# dc_q84_v2_v1.net
KiCad netlist of a schematic drawn in EAGLE
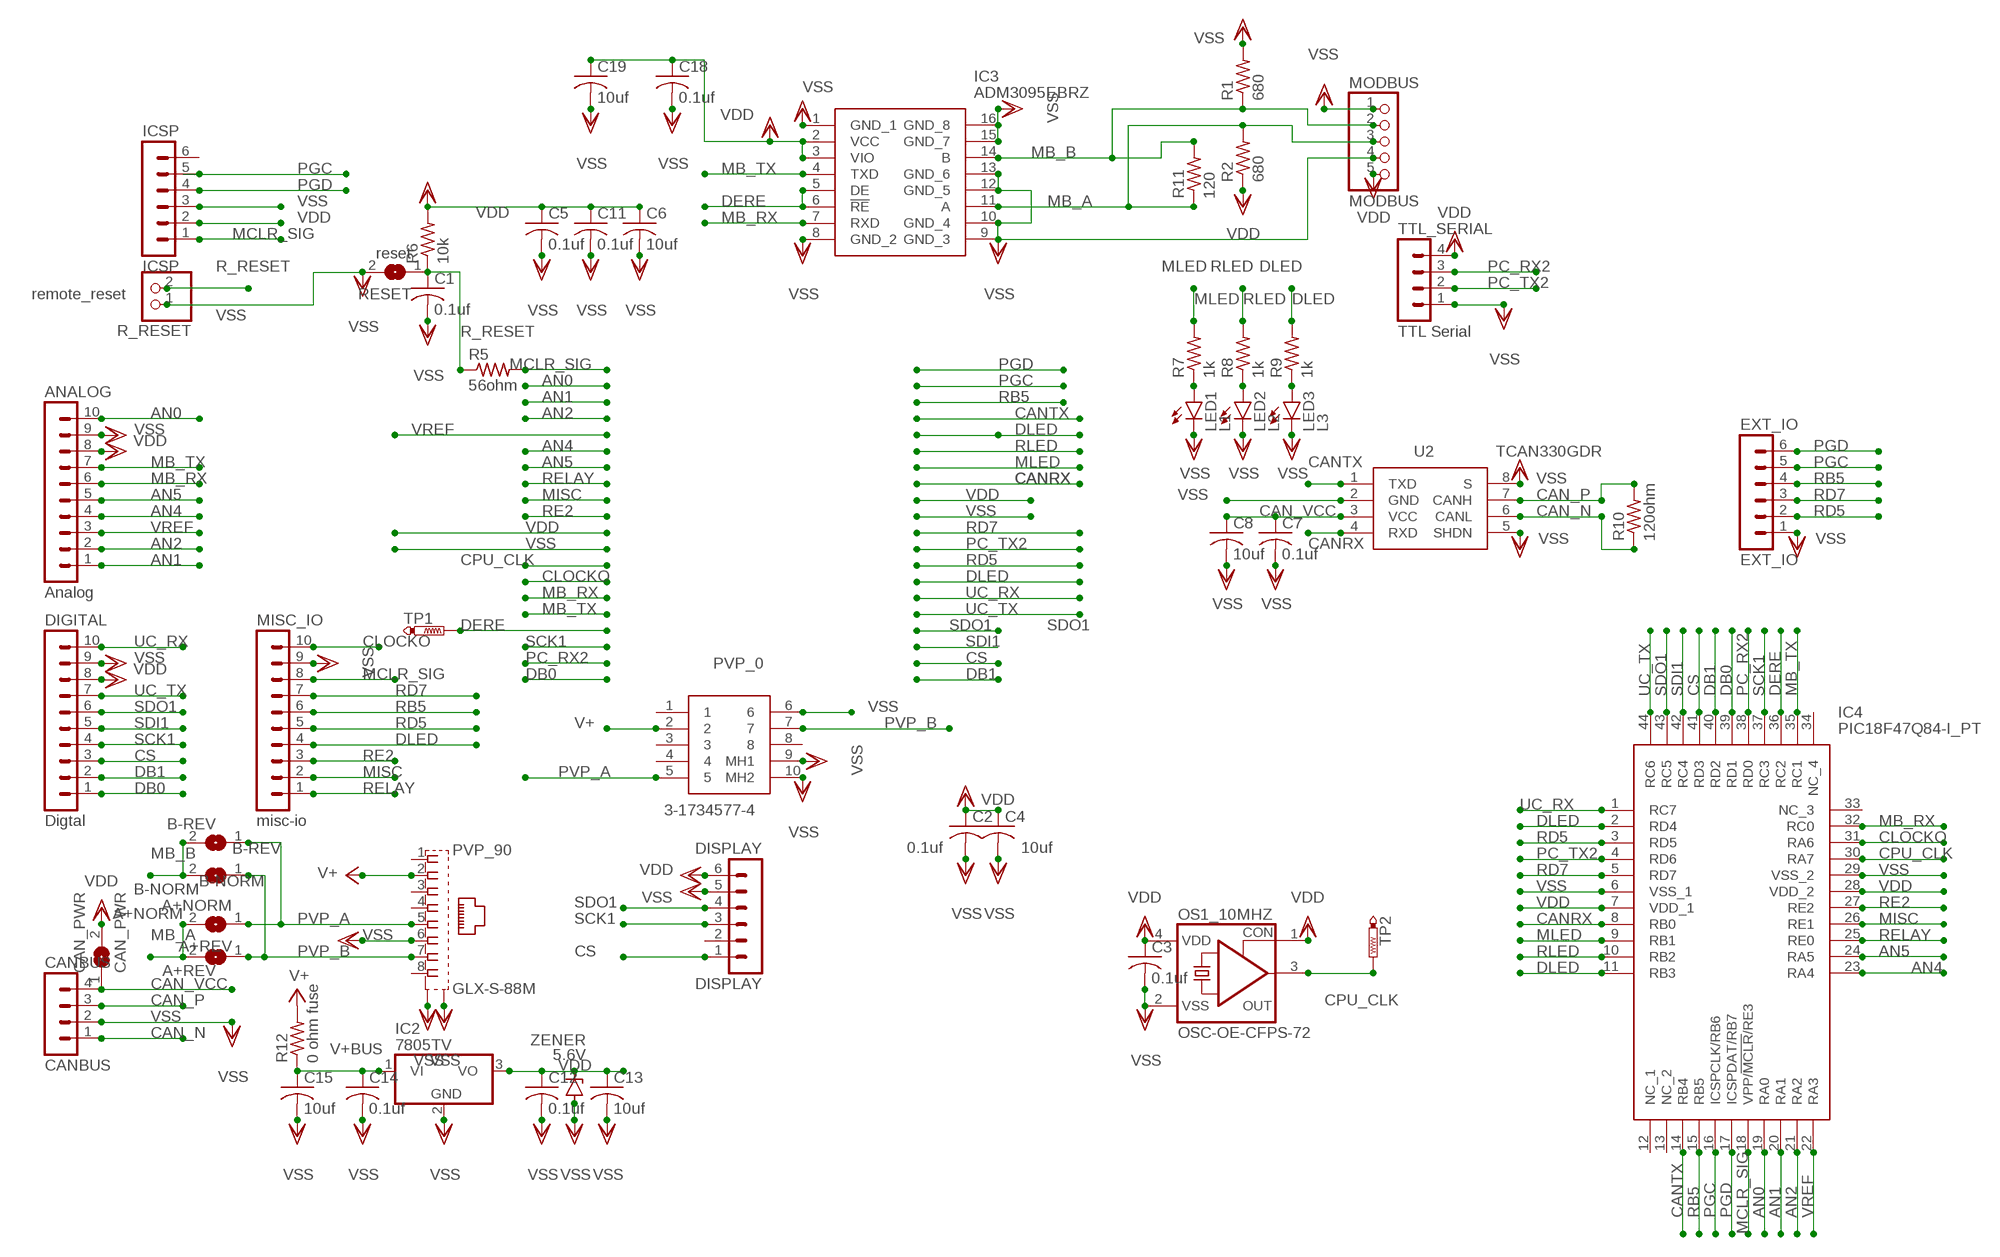
[diagram p0: schematic, sheet 1]

(export (version "E")
  (design (tool "Eeschema 10.0.6"))
  (components
    (comp (ref "A+NORM")
      (value "A+NORM")
      (footprint "eagle-import:SJ")
      (libsource (lib "eagle-import") (part "SJ"))
    )
    (comp (ref "A+REV")
      (value "A+REV")
      (footprint "eagle-import:SJ")
      (libsource (lib "eagle-import") (part "SJ"))
    )
    (comp (ref "ANALOG")
      (value "Analog")
      (footprint "eagle-import:MA10-1")
      (libsource (lib "eagle-import") (part "MA10-1"))
    )
    (comp (ref "B-NORM")
      (value "B-NORM")
      (footprint "eagle-import:SJ")
      (libsource (lib "eagle-import") (part "SJ"))
    )
    (comp (ref "B-REV")
      (value "B-REV")
      (footprint "eagle-import:SJ")
      (libsource (lib "eagle-import") (part "SJ"))
    )
    (comp (ref "C1")
      (value "0.1uf")
      (footprint "eagle-import:C0805")
      (libsource (lib "eagle-import") (part "C-USC0805"))
    )
    (comp (ref "C2")
      (value "0.1uf")
      (footprint "eagle-import:C0805")
      (libsource (lib "eagle-import") (part "C-USC0805"))
    )
    (comp (ref "C3")
      (value "0.1uf")
      (footprint "eagle-import:C0805")
      (libsource (lib "eagle-import") (part "C-USC0805"))
    )
    (comp (ref "C4")
      (value "10uf")
      (footprint "eagle-import:C0805")
      (libsource (lib "eagle-import") (part "C-USC0805"))
    )
    (comp (ref "C5")
      (value "0.1uf")
      (footprint "eagle-import:C0805")
      (libsource (lib "eagle-import") (part "C-USC0805"))
    )
    (comp (ref "C6")
      (value "10uf")
      (footprint "eagle-import:C0805")
      (libsource (lib "eagle-import") (part "C-USC0805"))
    )
    (comp (ref "C7")
      (value "0.1uf")
      (footprint "eagle-import:C0805")
      (libsource (lib "eagle-import") (part "C-USC0805"))
    )
    (comp (ref "C8")
      (value "10uf")
      (footprint "eagle-import:C0805")
      (libsource (lib "eagle-import") (part "C-USC0805"))
    )
    (comp (ref "C11")
      (value "0.1uf")
      (footprint "eagle-import:C0805")
      (libsource (lib "eagle-import") (part "C-USC0805"))
    )
    (comp (ref "C12")
      (value "0.1uf")
      (footprint "eagle-import:C0805")
      (libsource (lib "eagle-import") (part "C-USC0805"))
    )
    (comp (ref "C13")
      (value "10uf")
      (footprint "eagle-import:C0805")
      (libsource (lib "eagle-import") (part "C-USC0805"))
    )
    (comp (ref "C14")
      (value "0.1uf")
      (footprint "eagle-import:C0805")
      (libsource (lib "eagle-import") (part "C-USC0805"))
    )
    (comp (ref "C15")
      (value "10uf")
      (footprint "eagle-import:C0805")
      (libsource (lib "eagle-import") (part "C-USC0805"))
    )
    (comp (ref "C18")
      (value "0.1uf")
      (footprint "eagle-import:C0805")
      (libsource (lib "eagle-import") (part "C-USC0805"))
    )
    (comp (ref "C19")
      (value "10uf")
      (footprint "eagle-import:C0805")
      (libsource (lib "eagle-import") (part "C-USC0805"))
    )
    (comp (ref "CANBUS")
      (value "CANBUS")
      (footprint "eagle-import:MA04-1")
      (libsource (lib "eagle-import") (part "MA04-1"))
    )
    (comp (ref "CAN_PWR")
      (value "CAN_PWR")
      (footprint "eagle-import:SJ")
      (libsource (lib "eagle-import") (part "SJ"))
    )
    (comp (ref "DIGITAL")
      (value "Digtal")
      (footprint "eagle-import:MA10-1")
      (libsource (lib "eagle-import") (part "MA10-1"))
    )
    (comp (ref "DISPLAY")
      (value "DISPLAY")
      (footprint "eagle-import:MA06-1")
      (libsource (lib "eagle-import") (part "MA06-1"))
    )
    (comp (ref "EXT_IO")
      (value "EXT_IO")
      (footprint "eagle-import:MA06-1")
      (libsource (lib "eagle-import") (part "MA06-1"))
    )
    (comp (ref "IC2")
      (value "7805TV")
      (footprint "eagle-import:TO220V")
      (libsource (lib "eagle-import") (part "78TV05"))
    )
    (comp (ref "IC3")
      (value "ADM3095EBRZ")
      (footprint "eagle-import:SOIC127P600X175-16N")
      (fields (field (name "MOUSER_PART_NUMBER") "584-ADM3095EBRZ"))
      (libsource (lib "eagle-import") (part "ADM3095EBRZ"))
    )
    (comp (ref "IC4")
      (value "PIC18F47Q84-I_PT")
      (footprint "eagle-import:QFP80P1200X1200X120-44N")
      (fields
        (field (name "MANUFACTURER_PART_NUMBER") "PIC18F47Q84-I/PT")
        (field (name "MOUSER_PART_NUMBER") "579-PIC18F47Q84-I/PT")
      )
      (libsource (lib "eagle-import") (part "PIC18F47Q84-I_PT"))
    )
    (comp (ref "ICSP")
      (value "ICSP")
      (footprint "eagle-import:MA06-1")
      (libsource (lib "eagle-import") (part "MA06-1"))
    )
    (comp (ref "LED1")
      (value "L1")
      (footprint "eagle-import:CHIPLED_0805")
      (libsource (lib "eagle-import") (part "LEDCHIPLED_0805"))
    )
    (comp (ref "LED2")
      (value "L2")
      (footprint "eagle-import:CHIPLED_0805")
      (libsource (lib "eagle-import") (part "LEDCHIPLED_0805"))
    )
    (comp (ref "LED3")
      (value "L3")
      (footprint "eagle-import:CHIPLED_0805")
      (libsource (lib "eagle-import") (part "LEDCHIPLED_0805"))
    )
    (comp (ref "MISC_IO")
      (value "misc-io")
      (footprint "eagle-import:MA10-1")
      (libsource (lib "eagle-import") (part "MA10-1"))
    )
    (comp (ref "MODBUS")
      (value "MODBUS")
      (footprint "eagle-import:1X05")
      (libsource (lib "eagle-import") (part "PINHD-1X5"))
    )
    (comp (ref "OS1_10MHZ")
      (value "OSC-OE-CFPS-72")
      (footprint "eagle-import:7.2X5.2-4-PAD")
      (libsource (lib "eagle-import") (part "OSC-OE-CFPS-72"))
    )
    (comp (ref "PVP_0")
      (value "3-1734577-4")
      (footprint "eagle-import:317345774")
      (fields (field (name "MOUSER_PART_NUMBER") "571-3-1734577-4"))
      (libsource (lib "eagle-import") (part "3-1734577-4"))
    )
    (comp (ref "PVP_90")
      (value "GLX-S-88M")
      (footprint "eagle-import:GLX-S-88M")
      (libsource (lib "eagle-import") (part "GLX-S-88M"))
    )
    (comp (ref "R1")
      (value "680")
      (footprint "eagle-import:R0805")
      (libsource (lib "eagle-import") (part "R-US_R0805"))
    )
    (comp (ref "R2")
      (value "680")
      (footprint "eagle-import:R0805")
      (libsource (lib "eagle-import") (part "R-US_R0805"))
    )
    (comp (ref "R5")
      (value "56ohm")
      (footprint "eagle-import:R0805")
      (libsource (lib "eagle-import") (part "R-US_R0805"))
    )
    (comp (ref "R6")
      (value "10k")
      (footprint "eagle-import:R0805")
      (libsource (lib "eagle-import") (part "R-US_R0805"))
    )
    (comp (ref "R7")
      (value "1k")
      (footprint "eagle-import:R0805")
      (libsource (lib "eagle-import") (part "R-US_R0805"))
    )
    (comp (ref "R8")
      (value "1k")
      (footprint "eagle-import:R0805")
      (libsource (lib "eagle-import") (part "R-US_R0805"))
    )
    (comp (ref "R9")
      (value "1k")
      (footprint "eagle-import:R0805")
      (libsource (lib "eagle-import") (part "R-US_R0805"))
    )
    (comp (ref "R10")
      (value "120ohm")
      (footprint "eagle-import:R0805")
      (libsource (lib "eagle-import") (part "R-US_R0805"))
    )
    (comp (ref "R11")
      (value "120")
      (footprint "eagle-import:R0805")
      (libsource (lib "eagle-import") (part "R-US_R0805"))
    )
    (comp (ref "R12")
      (value "0 ohm fuse")
      (footprint "eagle-import:R1206")
      (libsource (lib "eagle-import") (part "R-US_R1206"))
    )
    (comp (ref "RESET")
      (value "reset")
      (footprint "eagle-import:SJ")
      (libsource (lib "eagle-import") (part "SJ"))
    )
    (comp (ref "R_RESET")
      (value "remote_reset")
      (footprint "eagle-import:1X02")
      (libsource (lib "eagle-import") (part "PINHD-1X2"))
    )
    (comp (ref "TP1")
      (value "PTR1PAD1-13")
      (footprint "eagle-import:P1-13")
      (libsource (lib "eagle-import") (part "PTR1PAD1-13"))
    )
    (comp (ref "TP2")
      (value "PTR1PAD1-13")
      (footprint "eagle-import:P1-13")
      (libsource (lib "eagle-import") (part "PTR1PAD1-13"))
    )
    (comp (ref "TTL_SERIAL")
      (value "TTL Serial")
      (footprint "eagle-import:MA04-1")
      (libsource (lib "eagle-import") (part "MA04-1"))
    )
    (comp (ref "U2")
      (value "TCAN330GDR")
      (footprint "eagle-import:SOIC127P600X175-8N")
      (fields (field (name "MOUSER_PART_NUMBER") "595-TCAN330GDR"))
      (libsource (lib "eagle-import") (part "TCAN330GDR"))
    )
    (comp (ref "ZENER")
      (value "5.6V")
      (footprint "eagle-import:SMB")
      (libsource (lib "eagle-import") (part "ZENER-DIODESMB"))
    )
  )
  (nets
    (net (code "1") (name "/AN0") (class "Default")
      (node (ref "ANALOG") (pin "10") (pinfunction "10_10") (pintype "passive"))
      (node (ref "IC4") (pin "19") (pinfunction "RA0_19") (pintype "bidirectional"))
    )
    (net (code "2") (name "/AN1") (class "Default")
      (node (ref "ANALOG") (pin "1") (pinfunction "1_1") (pintype "passive"))
      (node (ref "IC4") (pin "20") (pinfunction "RA1_20") (pintype "bidirectional"))
    )
    (net (code "3") (name "/AN2") (class "Default")
      (node (ref "ANALOG") (pin "2") (pinfunction "2_2") (pintype "passive"))
      (node (ref "IC4") (pin "21") (pinfunction "RA2_21") (pintype "bidirectional"))
    )
    (net (code "4") (name "/AN4") (class "Default")
      (node (ref "ANALOG") (pin "4") (pinfunction "4_4") (pintype "passive"))
      (node (ref "IC4") (pin "23") (pinfunction "RA4_23") (pintype "bidirectional"))
    )
    (net (code "5") (name "/AN5") (class "Default")
      (node (ref "ANALOG") (pin "5") (pinfunction "5_5") (pintype "passive"))
      (node (ref "IC4") (pin "24") (pinfunction "RA5_24") (pintype "bidirectional"))
    )
    (net (code "6") (name "/CANRX") (class "Default")
      (node (ref "IC4") (pin "8") (pinfunction "RB0_8") (pintype "bidirectional"))
      (node (ref "U2") (pin "4") (pinfunction "RXD_4") (pintype "output"))
    )
    (net (code "7") (name "/CANTX") (class "Default")
      (node (ref "IC4") (pin "14") (pinfunction "RB4_14") (pintype "bidirectional"))
      (node (ref "U2") (pin "1") (pinfunction "TXD_1") (pintype "input"))
    )
    (net (code "8") (name "/CAN_N") (class "Default")
      (node (ref "CANBUS") (pin "1") (pinfunction "1_1") (pintype "passive"))
      (node (ref "R10") (pin "1") (pinfunction "1_1") (pintype "passive"))
      (node (ref "U2") (pin "6") (pinfunction "CANL_6") (pintype "bidirectional"))
    )
    (net (code "9") (name "/CAN_P") (class "Default")
      (node (ref "CANBUS") (pin "3") (pinfunction "3_3") (pintype "passive"))
      (node (ref "R10") (pin "2") (pinfunction "2_2") (pintype "passive"))
      (node (ref "U2") (pin "7") (pinfunction "CANH_7") (pintype "bidirectional"))
    )
    (net (code "10") (name "/CAN_VCC") (class "Default")
      (node (ref "C7") (pin "1") (pinfunction "1_1") (pintype "passive"))
      (node (ref "C8") (pin "1") (pinfunction "1_1") (pintype "passive"))
      (node (ref "CANBUS") (pin "4") (pinfunction "4_4") (pintype "passive"))
      (node (ref "CAN_PWR") (pin "1") (pinfunction "1_1") (pintype "passive"))
      (node (ref "U2") (pin "3") (pinfunction "VCC_3") (pintype "power_in"))
    )
    (net (code "11") (name "/CLOCKO") (class "Default")
      (node (ref "IC4") (pin "31") (pinfunction "RA6_31") (pintype "bidirectional"))
      (node (ref "MISC_IO") (pin "10") (pinfunction "10_10") (pintype "passive"))
    )
    (net (code "12") (name "/CPU_CLK") (class "Default")
      (node (ref "IC4") (pin "30") (pinfunction "RA7_30") (pintype "bidirectional"))
      (node (ref "OS1_10MHZ") (pin "3") (pinfunction "OUT_3") (pintype "output"))
      (node (ref "TP2") (pin "TP") (pinfunction "TP_TP") (pintype "input"))
    )
    (net (code "13") (name "/CS") (class "Default")
      (node (ref "DIGITAL") (pin "3") (pinfunction "3_3") (pintype "passive"))
      (node (ref "DISPLAY") (pin "1") (pinfunction "1_1") (pintype "passive"))
      (node (ref "IC4") (pin "41") (pinfunction "RD3_41") (pintype "bidirectional"))
    )
    (net (code "14") (name "/DB0") (class "Default")
      (node (ref "DIGITAL") (pin "1") (pinfunction "1_1") (pintype "passive"))
      (node (ref "IC4") (pin "39") (pinfunction "RD1_39") (pintype "bidirectional"))
    )
    (net (code "15") (name "/DB1") (class "Default")
      (node (ref "DIGITAL") (pin "2") (pinfunction "2_2") (pintype "passive"))
      (node (ref "IC4") (pin "40") (pinfunction "RD2_40") (pintype "bidirectional"))
    )
    (net (code "16") (name "/DERE") (class "Default")
      (node (ref "IC3") (pin "5") (pinfunction "DE_5") (pintype "input"))
      (node (ref "IC3") (pin "6") (pinfunction "~{RE}_6") (pintype "input"))
      (node (ref "IC4") (pin "36") (pinfunction "RC2_36") (pintype "bidirectional"))
      (node (ref "TP1") (pin "TP") (pinfunction "TP_TP") (pintype "input"))
    )
    (net (code "17") (name "/DLED") (class "Default")
      (node (ref "IC4") (pin "11") (pinfunction "RB3_11") (pintype "bidirectional"))
      (node (ref "IC4") (pin "2") (pinfunction "RD4_2") (pintype "bidirectional"))
      (node (ref "MISC_IO") (pin "4") (pinfunction "4_4") (pintype "passive"))
      (node (ref "R9") (pin "2") (pinfunction "2_2") (pintype "passive"))
    )
    (net (code "18") (name "/MB_A") (class "Default")
      (node (ref "A+NORM") (pin "2") (pinfunction "2_2") (pintype "passive"))
      (node (ref "A+REV") (pin "2") (pinfunction "2_2") (pintype "passive"))
      (node (ref "IC3") (pin "11") (pinfunction "A_11") (pintype "bidirectional"))
      (node (ref "MODBUS") (pin "3") (pinfunction "3_3") (pintype "passive"))
      (node (ref "R11") (pin "1") (pinfunction "1_1") (pintype "passive"))
      (node (ref "R2") (pin "2") (pinfunction "2_2") (pintype "passive"))
    )
    (net (code "19") (name "/MB_B") (class "Default")
      (node (ref "B-NORM") (pin "2") (pinfunction "2_2") (pintype "passive"))
      (node (ref "B-REV") (pin "2") (pinfunction "2_2") (pintype "passive"))
      (node (ref "IC3") (pin "14") (pinfunction "B_14") (pintype "bidirectional"))
      (node (ref "MODBUS") (pin "2") (pinfunction "2_2") (pintype "passive"))
      (node (ref "R1") (pin "1") (pinfunction "1_1") (pintype "passive"))
      (node (ref "R11") (pin "2") (pinfunction "2_2") (pintype "passive"))
    )
    (net (code "20") (name "/MB_RX") (class "Default")
      (node (ref "ANALOG") (pin "6") (pinfunction "6_6") (pintype "passive"))
      (node (ref "IC3") (pin "7") (pinfunction "RXD_7") (pintype "output"))
      (node (ref "IC4") (pin "32") (pinfunction "RC0_32") (pintype "bidirectional"))
    )
    (net (code "21") (name "/MB_TX") (class "Default")
      (node (ref "ANALOG") (pin "7") (pinfunction "7_7") (pintype "passive"))
      (node (ref "IC3") (pin "4") (pinfunction "TXD_4") (pintype "input"))
      (node (ref "IC4") (pin "35") (pinfunction "RC1_35") (pintype "bidirectional"))
    )
    (net (code "22") (name "/MCLR_SIG") (class "Default")
      (node (ref "IC4") (pin "18") (pinfunction "VPP/~{MCLR}/RE3_18") (pintype "bidirectional"))
      (node (ref "ICSP") (pin "1") (pinfunction "1_1") (pintype "passive"))
      (node (ref "MISC_IO") (pin "8") (pinfunction "8_8") (pintype "passive"))
      (node (ref "R5") (pin "2") (pinfunction "2_2") (pintype "passive"))
    )
    (net (code "23") (name "/MISC") (class "Default")
      (node (ref "IC4") (pin "26") (pinfunction "RE1_26") (pintype "bidirectional"))
      (node (ref "MISC_IO") (pin "2") (pinfunction "2_2") (pintype "passive"))
    )
    (net (code "24") (name "/MLED") (class "Default")
      (node (ref "IC4") (pin "9") (pinfunction "RB1_9") (pintype "bidirectional"))
      (node (ref "R7") (pin "2") (pinfunction "2_2") (pintype "passive"))
    )
    (net (code "25") (name "/PC_RX2") (class "Default")
      (node (ref "IC4") (pin "38") (pinfunction "RD0_38") (pintype "bidirectional"))
      (node (ref "TTL_SERIAL") (pin "3") (pinfunction "3_3") (pintype "passive"))
    )
    (net (code "26") (name "/PC_TX2") (class "Default")
      (node (ref "IC4") (pin "4") (pinfunction "RD6_4") (pintype "bidirectional"))
      (node (ref "TTL_SERIAL") (pin "2") (pinfunction "2_2") (pintype "passive"))
    )
    (net (code "27") (name "/PGC") (class "Default")
      (node (ref "EXT_IO") (pin "5") (pinfunction "5_5") (pintype "passive"))
      (node (ref "IC4") (pin "16") (pinfunction "ICSPCLK/RB6_16") (pintype "bidirectional"))
      (node (ref "ICSP") (pin "5") (pinfunction "5_5") (pintype "passive"))
    )
    (net (code "28") (name "/PGD") (class "Default")
      (node (ref "EXT_IO") (pin "6") (pinfunction "6_6") (pintype "passive"))
      (node (ref "IC4") (pin "17") (pinfunction "ICSPDAT/RB7_17") (pintype "bidirectional"))
      (node (ref "ICSP") (pin "4") (pinfunction "4_4") (pintype "passive"))
    )
    (net (code "29") (name "/PVP_A") (class "Default")
      (node (ref "A+NORM") (pin "1") (pinfunction "1_1") (pintype "passive"))
      (node (ref "B-REV") (pin "1") (pinfunction "1_1") (pintype "passive"))
      (node (ref "PVP_0") (pin "5") (pinfunction "5_5") (pintype "bidirectional"))
      (node (ref "PVP_90") (pin "5") (pinfunction "5_5") (pintype "passive"))
    )
    (net (code "30") (name "/PVP_B") (class "Default")
      (node (ref "A+REV") (pin "1") (pinfunction "1_1") (pintype "passive"))
      (node (ref "B-NORM") (pin "1") (pinfunction "1_1") (pintype "passive"))
      (node (ref "PVP_0") (pin "7") (pinfunction "7_7") (pintype "bidirectional"))
      (node (ref "PVP_90") (pin "7") (pinfunction "7_7") (pintype "passive"))
    )
    (net (code "31") (name "/RB5") (class "Default")
      (node (ref "EXT_IO") (pin "4") (pinfunction "4_4") (pintype "passive"))
      (node (ref "IC4") (pin "15") (pinfunction "RB5_15") (pintype "bidirectional"))
      (node (ref "MISC_IO") (pin "6") (pinfunction "6_6") (pintype "passive"))
    )
    (net (code "32") (name "/RD5") (class "Default")
      (node (ref "EXT_IO") (pin "2") (pinfunction "2_2") (pintype "passive"))
      (node (ref "IC4") (pin "3") (pinfunction "RD5_3") (pintype "bidirectional"))
      (node (ref "MISC_IO") (pin "5") (pinfunction "5_5") (pintype "passive"))
    )
    (net (code "33") (name "/RD7") (class "Default")
      (node (ref "EXT_IO") (pin "3") (pinfunction "3_3") (pintype "passive"))
      (node (ref "IC4") (pin "5") (pinfunction "RD7_5") (pintype "bidirectional"))
      (node (ref "MISC_IO") (pin "7") (pinfunction "7_7") (pintype "passive"))
    )
    (net (code "34") (name "/RE2") (class "Default")
      (node (ref "IC4") (pin "27") (pinfunction "RE2_27") (pintype "bidirectional"))
      (node (ref "MISC_IO") (pin "3") (pinfunction "3_3") (pintype "passive"))
    )
    (net (code "35") (name "/RELAY") (class "Default")
      (node (ref "IC4") (pin "25") (pinfunction "RE0_25") (pintype "bidirectional"))
      (node (ref "MISC_IO") (pin "1") (pinfunction "1_1") (pintype "passive"))
    )
    (net (code "36") (name "/RLED") (class "Default")
      (node (ref "IC4") (pin "10") (pinfunction "RB2_10") (pintype "bidirectional"))
      (node (ref "R8") (pin "2") (pinfunction "2_2") (pintype "passive"))
    )
    (net (code "37") (name "/R_RESET") (class "Default")
      (node (ref "C1") (pin "1") (pinfunction "1_1") (pintype "passive"))
      (node (ref "R5") (pin "1") (pinfunction "1_1") (pintype "passive"))
      (node (ref "R6") (pin "1") (pinfunction "1_1") (pintype "passive"))
      (node (ref "RESET") (pin "1") (pinfunction "1_1") (pintype "passive"))
      (node (ref "R_RESET") (pin "2") (pinfunction "2_2") (pintype "passive"))
    )
    (net (code "38") (name "/SCK1") (class "Default")
      (node (ref "DIGITAL") (pin "4") (pinfunction "4_4") (pintype "passive"))
      (node (ref "DISPLAY") (pin "3") (pinfunction "3_3") (pintype "passive"))
      (node (ref "IC4") (pin "37") (pinfunction "RC3_37") (pintype "bidirectional"))
    )
    (net (code "39") (name "/SDI1") (class "Default")
      (node (ref "DIGITAL") (pin "5") (pinfunction "5_5") (pintype "passive"))
      (node (ref "IC4") (pin "42") (pinfunction "RC4_42") (pintype "bidirectional"))
    )
    (net (code "40") (name "/SDO1") (class "Default")
      (node (ref "DIGITAL") (pin "6") (pinfunction "6_6") (pintype "passive"))
      (node (ref "DISPLAY") (pin "4") (pinfunction "4_4") (pintype "passive"))
      (node (ref "IC4") (pin "43") (pinfunction "RC5_43") (pintype "bidirectional"))
    )
    (net (code "41") (name "/UC_RX") (class "Default")
      (node (ref "DIGITAL") (pin "10") (pinfunction "10_10") (pintype "passive"))
      (node (ref "IC4") (pin "1") (pinfunction "RC7_1") (pintype "bidirectional"))
    )
    (net (code "42") (name "/UC_TX") (class "Default")
      (node (ref "DIGITAL") (pin "7") (pinfunction "7_7") (pintype "passive"))
      (node (ref "IC4") (pin "44") (pinfunction "RC6_44") (pintype "bidirectional"))
    )
    (net (code "43") (name "/V+BUS") (class "Default")
      (node (ref "C14") (pin "1") (pinfunction "1_1") (pintype "passive"))
      (node (ref "C15") (pin "1") (pinfunction "1_1") (pintype "passive"))
      (node (ref "IC2") (pin "1") (pinfunction "VI_1") (pintype "input"))
      (node (ref "R12") (pin "1") (pinfunction "1_1") (pintype "passive"))
    )
    (net (code "44") (name "/VREF") (class "Default")
      (node (ref "ANALOG") (pin "3") (pinfunction "3_3") (pintype "passive"))
      (node (ref "IC4") (pin "22") (pinfunction "RA3_22") (pintype "bidirectional"))
    )
    (net (code "45") (name "Net-(LED1-PadA)") (class "Default")
      (node (ref "LED1") (pin "A") (pinfunction "A_A") (pintype "passive"))
      (node (ref "R7") (pin "1") (pinfunction "1_1") (pintype "passive"))
    )
    (net (code "46") (name "Net-(LED2-PadA)") (class "Default")
      (node (ref "LED2") (pin "A") (pinfunction "A_A") (pintype "passive"))
      (node (ref "R8") (pin "1") (pinfunction "1_1") (pintype "passive"))
    )
    (net (code "47") (name "Net-(LED3-PadA)") (class "Default")
      (node (ref "LED3") (pin "A") (pinfunction "A_A") (pintype "passive"))
      (node (ref "R9") (pin "1") (pinfunction "1_1") (pintype "passive"))
    )
    (net (code "48") (name "V+") (class "Default")
      (node (ref "PVP_0") (pin "2") (pinfunction "2_2") (pintype "bidirectional"))
      (node (ref "PVP_90") (pin "2") (pinfunction "2_2") (pintype "passive"))
      (node (ref "R12") (pin "2") (pinfunction "2_2") (pintype "passive"))
    )
    (net (code "49") (name "VDD") (class "Default")
      (node (ref "ANALOG") (pin "8") (pinfunction "8_8") (pintype "passive"))
      (node (ref "C11") (pin "1") (pinfunction "1_1") (pintype "passive"))
      (node (ref "C12") (pin "1") (pinfunction "1_1") (pintype "passive"))
      (node (ref "C13") (pin "1") (pinfunction "1_1") (pintype "passive"))
      (node (ref "C18") (pin "1") (pinfunction "1_1") (pintype "passive"))
      (node (ref "C19") (pin "1") (pinfunction "1_1") (pintype "passive"))
      (node (ref "C2") (pin "1") (pinfunction "1_1") (pintype "passive"))
      (node (ref "C3") (pin "1") (pinfunction "1_1") (pintype "passive"))
      (node (ref "C4") (pin "1") (pinfunction "1_1") (pintype "passive"))
      (node (ref "C5") (pin "1") (pinfunction "1_1") (pintype "passive"))
      (node (ref "C6") (pin "1") (pinfunction "1_1") (pintype "passive"))
      (node (ref "CAN_PWR") (pin "2") (pinfunction "2_2") (pintype "passive"))
      (node (ref "DIGITAL") (pin "8") (pinfunction "8_8") (pintype "passive"))
      (node (ref "DISPLAY") (pin "6") (pinfunction "6_6") (pintype "passive"))
      (node (ref "IC2") (pin "3") (pinfunction "VO_3") (pintype "passive"))
      (node (ref "IC3") (pin "2") (pinfunction "VCC_2") (pintype "power_in"))
      (node (ref "IC3") (pin "3") (pinfunction "VIO_3") (pintype "power_in"))
      (node (ref "IC4") (pin "28") (pinfunction "VDD_2_28") (pintype "bidirectional"))
      (node (ref "IC4") (pin "7") (pinfunction "VDD_1_7") (pintype "bidirectional"))
      (node (ref "ICSP") (pin "2") (pinfunction "2_2") (pintype "passive"))
      (node (ref "MODBUS") (pin "5") (pinfunction "5_5") (pintype "passive"))
      (node (ref "OS1_10MHZ") (pin "1") (pinfunction "CON_1") (pintype "input"))
      (node (ref "OS1_10MHZ") (pin "4") (pinfunction "VDD_4") (pintype "power_in"))
      (node (ref "R2") (pin "1") (pinfunction "1_1") (pintype "passive"))
      (node (ref "R6") (pin "2") (pinfunction "2_2") (pintype "passive"))
      (node (ref "TTL_SERIAL") (pin "4") (pinfunction "4_4") (pintype "passive"))
      (node (ref "ZENER") (pin "C") (pinfunction "C_C") (pintype "passive"))
    )
    (net (code "50") (name "VSS") (class "Default")
      (node (ref "ANALOG") (pin "9") (pinfunction "9_9") (pintype "passive"))
      (node (ref "C1") (pin "2") (pinfunction "2_2") (pintype "passive"))
      (node (ref "C11") (pin "2") (pinfunction "2_2") (pintype "passive"))
      (node (ref "C12") (pin "2") (pinfunction "2_2") (pintype "passive"))
      (node (ref "C13") (pin "2") (pinfunction "2_2") (pintype "passive"))
      (node (ref "C14") (pin "2") (pinfunction "2_2") (pintype "passive"))
      (node (ref "C15") (pin "2") (pinfunction "2_2") (pintype "passive"))
      (node (ref "C18") (pin "2") (pinfunction "2_2") (pintype "passive"))
      (node (ref "C19") (pin "2") (pinfunction "2_2") (pintype "passive"))
      (node (ref "C2") (pin "2") (pinfunction "2_2") (pintype "passive"))
      (node (ref "C3") (pin "2") (pinfunction "2_2") (pintype "passive"))
      (node (ref "C4") (pin "2") (pinfunction "2_2") (pintype "passive"))
      (node (ref "C5") (pin "2") (pinfunction "2_2") (pintype "passive"))
      (node (ref "C6") (pin "2") (pinfunction "2_2") (pintype "passive"))
      (node (ref "C7") (pin "2") (pinfunction "2_2") (pintype "passive"))
      (node (ref "C8") (pin "2") (pinfunction "2_2") (pintype "passive"))
      (node (ref "CANBUS") (pin "2") (pinfunction "2_2") (pintype "passive"))
      (node (ref "DIGITAL") (pin "9") (pinfunction "9_9") (pintype "passive"))
      (node (ref "DISPLAY") (pin "5") (pinfunction "5_5") (pintype "passive"))
      (node (ref "EXT_IO") (pin "1") (pinfunction "1_1") (pintype "passive"))
      (node (ref "IC2") (pin "2") (pinfunction "GND_2") (pintype "passive"))
      (node (ref "IC3") (pin "1") (pinfunction "GND_1_1") (pintype "power_in"))
      (node (ref "IC3") (pin "10") (pinfunction "GND_4_10") (pintype "power_in"))
      (node (ref "IC3") (pin "12") (pinfunction "GND_5_12") (pintype "power_in"))
      (node (ref "IC3") (pin "13") (pinfunction "GND_6_13") (pintype "power_in"))
      (node (ref "IC3") (pin "15") (pinfunction "GND_7_15") (pintype "power_in"))
      (node (ref "IC3") (pin "16") (pinfunction "GND_8_16") (pintype "power_in"))
      (node (ref "IC3") (pin "8") (pinfunction "GND_2_8") (pintype "power_in"))
      (node (ref "IC3") (pin "9") (pinfunction "GND_3_9") (pintype "power_in"))
      (node (ref "IC4") (pin "29") (pinfunction "VSS_2_29") (pintype "bidirectional"))
      (node (ref "IC4") (pin "6") (pinfunction "VSS_1_6") (pintype "bidirectional"))
      (node (ref "ICSP") (pin "3") (pinfunction "3_3") (pintype "passive"))
      (node (ref "LED1") (pin "C") (pinfunction "C_C") (pintype "passive"))
      (node (ref "LED2") (pin "C") (pinfunction "C_C") (pintype "passive"))
      (node (ref "LED3") (pin "C") (pinfunction "C_C") (pintype "passive"))
      (node (ref "MISC_IO") (pin "9") (pinfunction "9_9") (pintype "passive"))
      (node (ref "MODBUS") (pin "1") (pinfunction "1_1") (pintype "passive"))
      (node (ref "MODBUS") (pin "4") (pinfunction "4_4") (pintype "passive"))
      (node (ref "OS1_10MHZ") (pin "2") (pinfunction "VSS_2") (pintype "power_in"))
      (node (ref "PVP_0") (pin "10") (pinfunction "MH2_10") (pintype "bidirectional"))
      (node (ref "PVP_0") (pin "6") (pinfunction "6_6") (pintype "bidirectional"))
      (node (ref "PVP_0") (pin "9") (pinfunction "MH1_9") (pintype "bidirectional"))
      (node (ref "PVP_90") (pin "6") (pinfunction "6_6") (pintype "passive"))
      (node (ref "PVP_90") (pin "S1") (pinfunction "S1_S1") (pintype "passive"))
      (node (ref "PVP_90") (pin "S2") (pinfunction "S2_S2") (pintype "passive"))
      (node (ref "R1") (pin "2") (pinfunction "2_2") (pintype "passive"))
      (node (ref "RESET") (pin "2") (pinfunction "2_2") (pintype "passive"))
      (node (ref "R_RESET") (pin "1") (pinfunction "1_1") (pintype "passive"))
      (node (ref "TTL_SERIAL") (pin "1") (pinfunction "1_1") (pintype "passive"))
      (node (ref "U2") (pin "2") (pinfunction "GND_2") (pintype "power_in"))
      (node (ref "U2") (pin "5") (pinfunction "SHDN_5") (pintype "bidirectional"))
      (node (ref "U2") (pin "8") (pinfunction "S_8") (pintype "bidirectional"))
      (node (ref "ZENER") (pin "A") (pinfunction "A_A") (pintype "passive"))
    )
    (net (code "51") (name "unconnected-(DISPLAY-Pad2)") (class "Default")
      (node (ref "DISPLAY") (pin "2") (pinfunction "2_2") (pintype "passive"))
    )
    (net (code "52") (name "unconnected-(IC4-NC_1-Pad12)") (class "Default")
      (node (ref "IC4") (pin "12") (pinfunction "NC_1_12") (pintype "bidirectional"))
    )
    (net (code "53") (name "unconnected-(IC4-NC_2-Pad13)") (class "Default")
      (node (ref "IC4") (pin "13") (pinfunction "NC_2_13") (pintype "bidirectional"))
    )
    (net (code "54") (name "unconnected-(IC4-NC_3-Pad33)") (class "Default")
      (node (ref "IC4") (pin "33") (pinfunction "NC_3_33") (pintype "bidirectional"))
    )
    (net (code "55") (name "unconnected-(IC4-NC_4-Pad34)") (class "Default")
      (node (ref "IC4") (pin "34") (pinfunction "NC_4_34") (pintype "bidirectional"))
    )
    (net (code "56") (name "unconnected-(ICSP-Pad6)") (class "Default")
      (node (ref "ICSP") (pin "6") (pinfunction "6_6") (pintype "passive"))
    )
    (net (code "57") (name "unconnected-(PVP_0-Pad1)") (class "Default")
      (node (ref "PVP_0") (pin "1") (pinfunction "1_1") (pintype "bidirectional"))
    )
    (net (code "58") (name "unconnected-(PVP_0-Pad3)") (class "Default")
      (node (ref "PVP_0") (pin "3") (pinfunction "3_3") (pintype "bidirectional"))
    )
    (net (code "59") (name "unconnected-(PVP_0-Pad4)") (class "Default")
      (node (ref "PVP_0") (pin "4") (pinfunction "4_4") (pintype "bidirectional"))
    )
    (net (code "60") (name "unconnected-(PVP_0-Pad8)") (class "Default")
      (node (ref "PVP_0") (pin "8") (pinfunction "8_8") (pintype "bidirectional"))
    )
    (net (code "61") (name "unconnected-(PVP_90-Pad1)") (class "Default")
      (node (ref "PVP_90") (pin "1") (pinfunction "1_1") (pintype "passive"))
    )
    (net (code "62") (name "unconnected-(PVP_90-Pad3)") (class "Default")
      (node (ref "PVP_90") (pin "3") (pinfunction "3_3") (pintype "passive"))
    )
    (net (code "63") (name "unconnected-(PVP_90-Pad4)") (class "Default")
      (node (ref "PVP_90") (pin "4") (pinfunction "4_4") (pintype "passive"))
    )
    (net (code "64") (name "unconnected-(PVP_90-Pad8)") (class "Default")
      (node (ref "PVP_90") (pin "8") (pinfunction "8_8") (pintype "passive"))
    )
  )
)
